# 4_cpu.net
KiCad netlist of a schematic drawn in Altium Designer
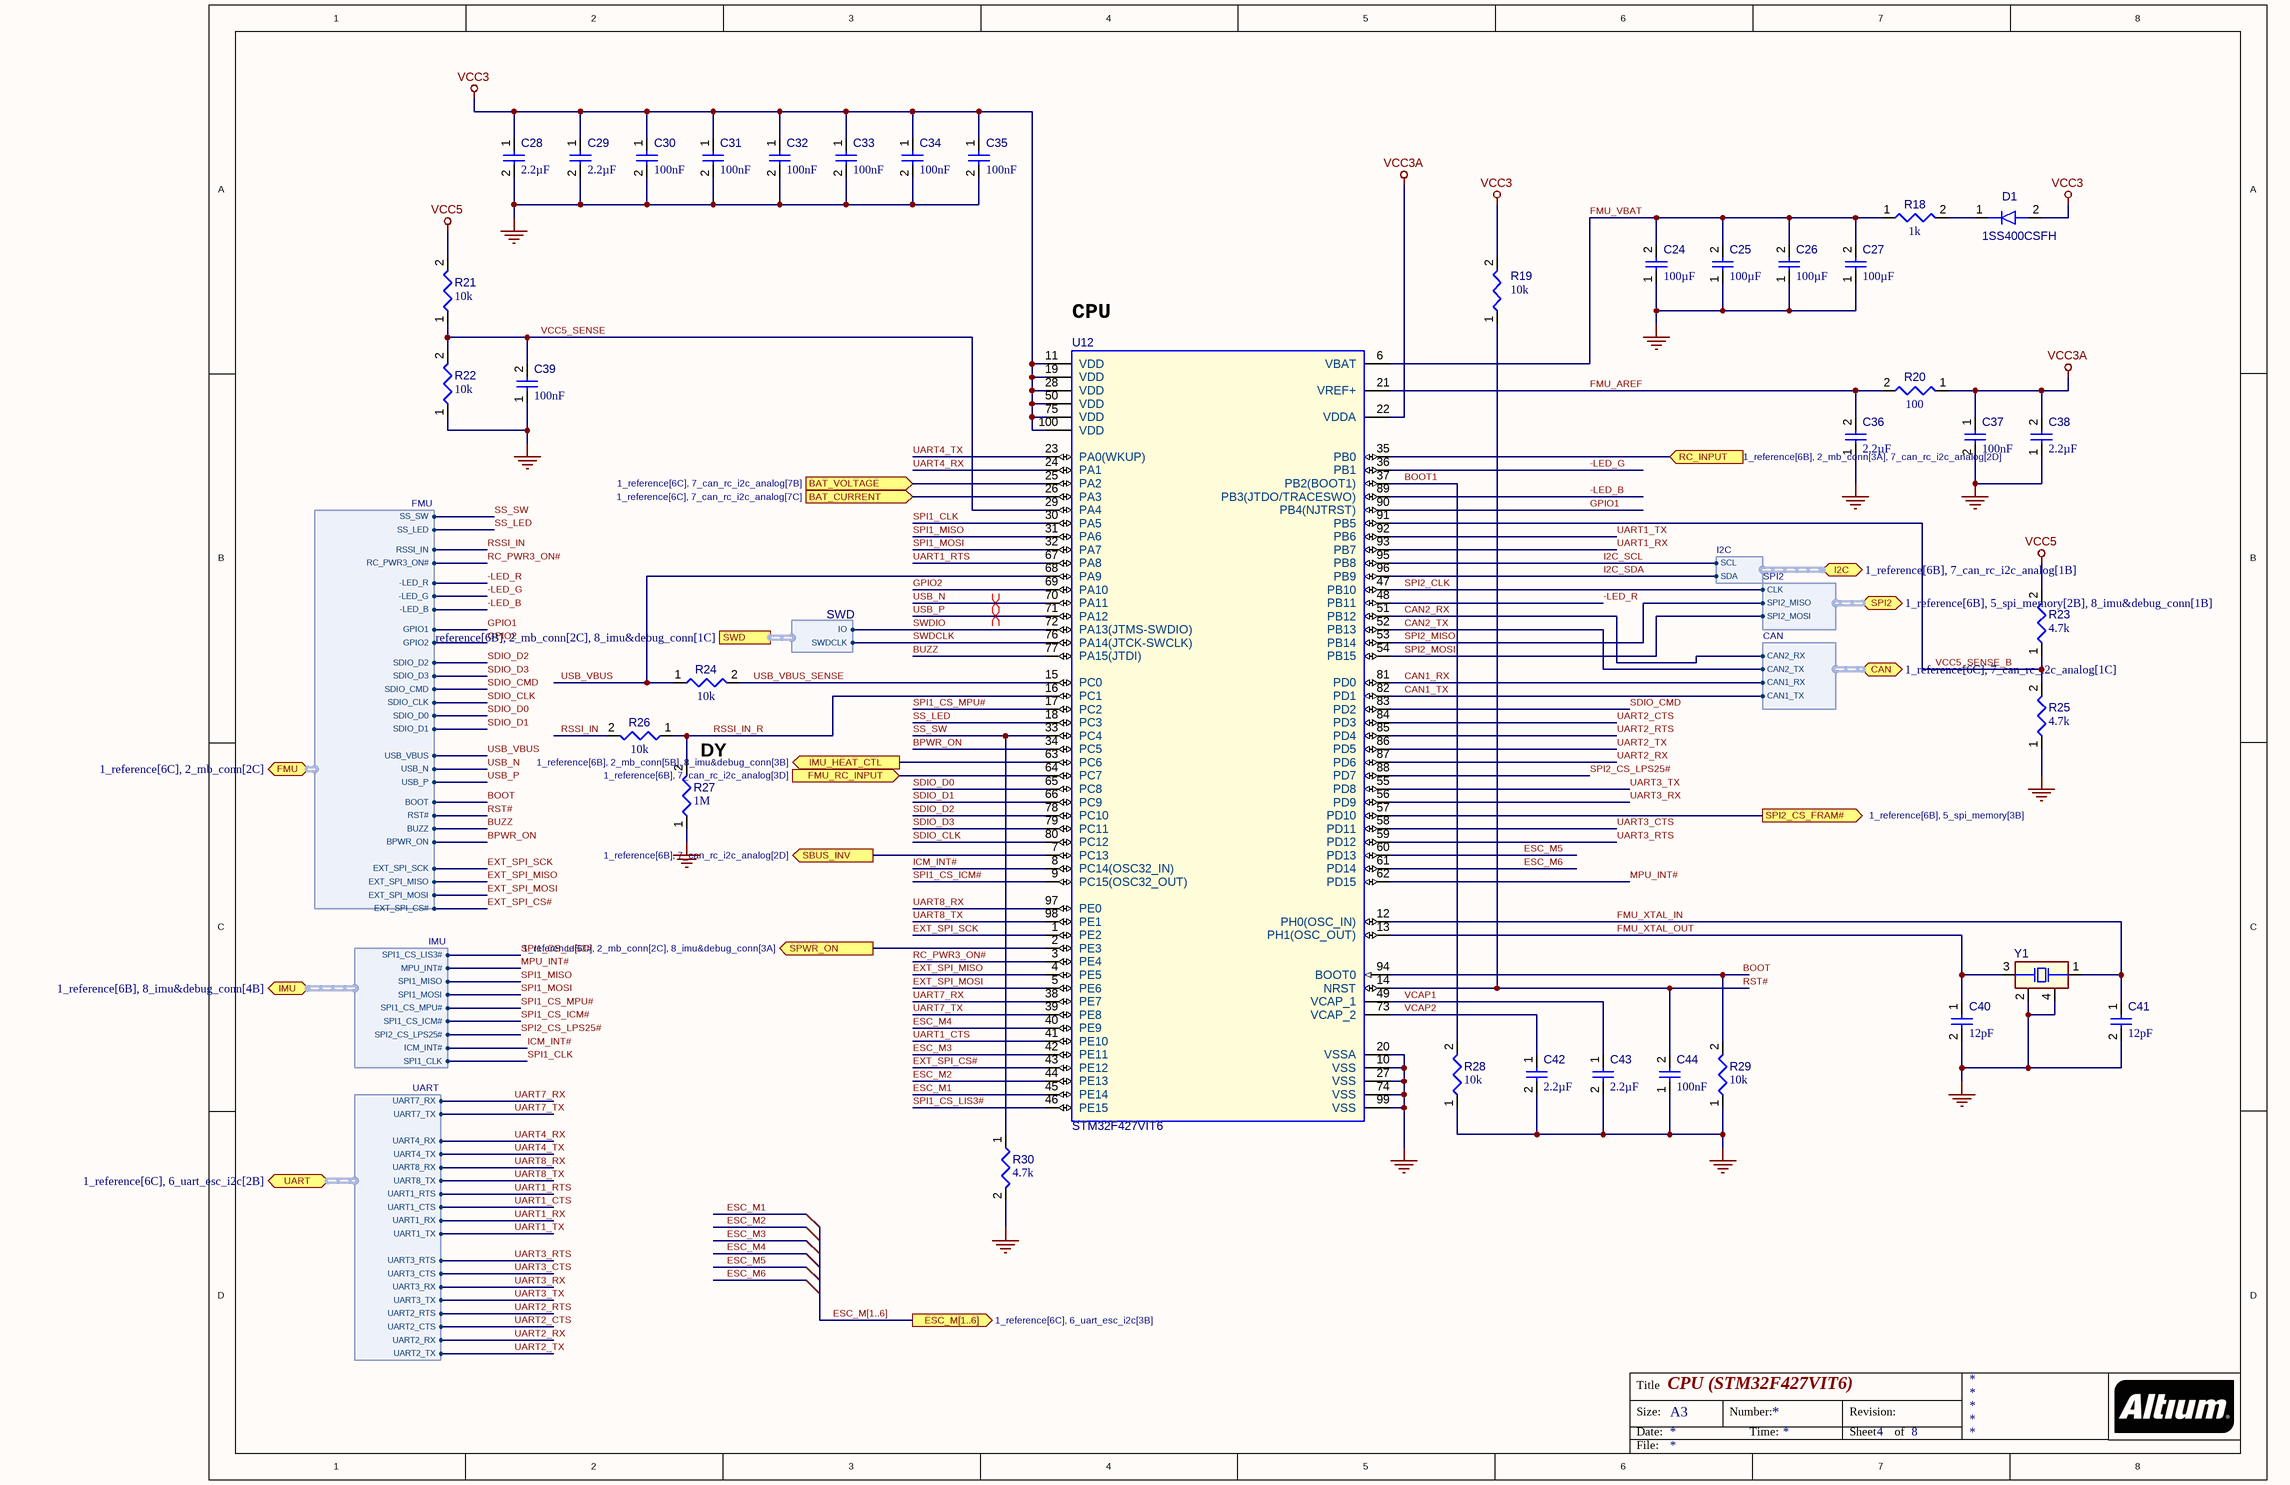
[diagram p0: 4_cpu.SchDoc]

(export (version "E")
  (design (tool "Eeschema 10.0.6"))
  (components
    (comp (ref "C24")
      (value "100µF")
      (footprint "CAPC0805(2012)145_L")
      (description "Chip Capacitor, 100µF +/-20%, 6.3V, 0805, Thickness 1.45 mm")
      (fields (field (name "TOLERANCE") "10%") (field (name "Comment") "Capacitor 100µF +/-20% 6.3V 0805"))
      (libsource (lib "<Company> Server") (part "CAP-NP-2"))
    )
    (comp (ref "C25")
      (value "100µF")
      (footprint "CAPC0805(2012)145_L")
      (description "Chip Capacitor, 100µF +/-20%, 6.3V, 0805, Thickness 1.45 mm")
      (fields (field (name "TOLERANCE") "10%") (field (name "Comment") "Capacitor 100µF +/-20% 6.3V 0805"))
      (libsource (lib "<Company> Server") (part "CAP-NP-2"))
    )
    (comp (ref "C26")
      (value "100µF")
      (footprint "CAPC0805(2012)145_L")
      (description "Chip Capacitor, 100µF +/-20%, 6.3V, 0805, Thickness 1.45 mm")
      (fields (field (name "TOLERANCE") "10%") (field (name "Comment") "Capacitor 100µF +/-20% 6.3V 0805"))
      (libsource (lib "<Company> Server") (part "CAP-NP-2"))
    )
    (comp (ref "C27")
      (value "100µF")
      (footprint "CAPC0805(2012)145_L")
      (description "Chip Capacitor, 100µF +/-20%, 6.3V, 0805, Thickness 1.45 mm")
      (fields (field (name "TOLERANCE") "10%") (field (name "Comment") "Capacitor 100µF +/-20% 6.3V 0805"))
      (libsource (lib "<Company> Server") (part "CAP-NP-2"))
    )
    (comp (ref "C28")
      (value "2.2µF")
      (footprint "CAPC0402(1005)60_L")
      (description "Chip Capacitor, 2,2µF +/-20%, 10V, 0402, Thickness 0.6 mm")
      (fields (field (name "TOLERANCE") "10%") (field (name "Comment") "Capacitor 2,2µF +/-20% 10V 0402"))
      (libsource (lib "<Company> Server") (part "CAP-NP-2"))
    )
    (comp (ref "C29")
      (value "2.2µF")
      (footprint "CAPC0402(1005)60_L")
      (description "Chip Capacitor, 2,2µF +/-20%, 10V, 0402, Thickness 0.6 mm")
      (fields (field (name "TOLERANCE") "10%") (field (name "Comment") "Capacitor 2,2µF +/-20% 10V 0402"))
      (libsource (lib "<Company> Server") (part "CAP-NP-2"))
    )
    (comp (ref "C30")
      (value "100nF")
      (footprint "CAPC0402(1005)60_L")
      (description "Chip Capacitor, 100nF +/-20%, 10V, 0402, Thickness 0.6 mm")
      (fields (field (name "TOLERANCE") "20%") (field (name "Comment") "Capacitor 100nF +/-20% 10V 0402"))
      (libsource (lib "<Company> Server") (part "CAP-NP-2"))
    )
    (comp (ref "C31")
      (value "100nF")
      (footprint "CAPC0402(1005)60_L")
      (description "Chip Capacitor, 100nF +/-20%, 10V, 0402, Thickness 0.6 mm")
      (fields (field (name "TOLERANCE") "20%") (field (name "Comment") "Capacitor 100nF +/-20% 10V 0402"))
      (libsource (lib "<Company> Server") (part "CAP-NP-2"))
    )
    (comp (ref "C32")
      (value "100nF")
      (footprint "CAPC0402(1005)60_L")
      (description "Chip Capacitor, 100nF +/-20%, 10V, 0402, Thickness 0.6 mm")
      (fields (field (name "TOLERANCE") "20%") (field (name "Comment") "Capacitor 100nF +/-20% 10V 0402"))
      (libsource (lib "<Company> Server") (part "CAP-NP-2"))
    )
    (comp (ref "C33")
      (value "100nF")
      (footprint "CAPC0402(1005)60_L")
      (description "Chip Capacitor, 100nF +/-20%, 10V, 0402, Thickness 0.6 mm")
      (fields (field (name "TOLERANCE") "20%") (field (name "Comment") "Capacitor 100nF +/-20% 10V 0402"))
      (libsource (lib "<Company> Server") (part "CAP-NP-2"))
    )
    (comp (ref "C34")
      (value "100nF")
      (footprint "CAPC0402(1005)60_L")
      (description "Chip Capacitor, 100nF +/-20%, 10V, 0402, Thickness 0.6 mm")
      (fields (field (name "TOLERANCE") "20%") (field (name "Comment") "Capacitor 100nF +/-20% 10V 0402"))
      (libsource (lib "<Company> Server") (part "CAP-NP-2"))
    )
    (comp (ref "C35")
      (value "100nF")
      (footprint "CAPC0402(1005)60_L")
      (description "Chip Capacitor, 100nF +/-20%, 10V, 0402, Thickness 0.6 mm")
      (fields (field (name "TOLERANCE") "20%") (field (name "Comment") "Capacitor 100nF +/-20% 10V 0402"))
      (libsource (lib "<Company> Server") (part "CAP-NP-2"))
    )
    (comp (ref "C36")
      (value "2.2µF")
      (footprint "CAPC0402(1005)60_L")
      (description "Chip Capacitor, 2,2µF +/-20%, 10V, 0402, Thickness 0.6 mm")
      (fields (field (name "TOLERANCE") "10%") (field (name "Comment") "Capacitor 2,2µF +/-20% 10V 0402"))
      (libsource (lib "<Company> Server") (part "CAP-NP-2"))
    )
    (comp (ref "C37")
      (value "100nF")
      (footprint "CAPC0402(1005)60_L")
      (description "Chip Capacitor, 100nF +/-20%, 10V, 0402, Thickness 0.6 mm")
      (fields (field (name "TOLERANCE") "20%") (field (name "Comment") "Capacitor 100nF +/-20% 10V 0402"))
      (libsource (lib "<Company> Server") (part "CAP-NP-2"))
    )
    (comp (ref "C38")
      (value "2.2µF")
      (footprint "CAPC0402(1005)60_L")
      (description "Chip Capacitor, 2,2µF +/-20%, 10V, 0402, Thickness 0.6 mm")
      (fields (field (name "TOLERANCE") "10%") (field (name "Comment") "Capacitor 2,2µF +/-20% 10V 0402"))
      (libsource (lib "<Company> Server") (part "CAP-NP-2"))
    )
    (comp (ref "C39")
      (value "100nF")
      (footprint "CAPC0402(1005)60_L")
      (description "Chip Capacitor, 100nF +/-20%, 10V, 0402, Thickness 0.6 mm")
      (fields (field (name "TOLERANCE") "20%") (field (name "Comment") "Capacitor 100nF +/-20% 10V 0402"))
      (libsource (lib "<Company> Server") (part "CAP-NP-2"))
    )
    (comp (ref "C40")
      (value "12pF")
      (footprint "CAPC0402(1005)33_L")
      (description "Chip Capacitor, 12pF +/-10%, 50V, 0402, Thickness 0.33 mm")
      (fields (field (name "TOLERANCE") "20%") (field (name "Comment") "Capacitor 12pF +/-10% 50V 0402"))
      (libsource (lib "<Company> Server") (part "CAP-NP-2"))
    )
    (comp (ref "C41")
      (value "12pF")
      (footprint "CAPC0402(1005)33_L")
      (description "Chip Capacitor, 12pF +/-10%, 50V, 0402, Thickness 0.33 mm")
      (fields (field (name "TOLERANCE") "20%") (field (name "Comment") "Capacitor 12pF +/-10% 50V 0402"))
      (libsource (lib "<Company> Server") (part "CAP-NP-2"))
    )
    (comp (ref "C42")
      (value "2.2µF")
      (footprint "CAPC0402(1005)60_L")
      (description "Chip Capacitor, 2,2µF +/-20%, 10V, 0402, Thickness 0.6 mm")
      (fields (field (name "TOLERANCE") "10%") (field (name "Comment") "Capacitor 2,2µF +/-20% 10V 0402"))
      (libsource (lib "<Company> Server") (part "CAP-NP-2"))
    )
    (comp (ref "C43")
      (value "2.2µF")
      (footprint "CAPC0402(1005)60_L")
      (description "Chip Capacitor, 2,2µF +/-20%, 10V, 0402, Thickness 0.6 mm")
      (fields (field (name "TOLERANCE") "10%") (field (name "Comment") "Capacitor 2,2µF +/-20% 10V 0402"))
      (libsource (lib "<Company> Server") (part "CAP-NP-2"))
    )
    (comp (ref "C44")
      (value "100nF")
      (footprint "CAPC0402(1005)60_L")
      (description "Chip Capacitor, 100nF +/-20%, 10V, 0402, Thickness 0.6 mm")
      (fields (field (name "TOLERANCE") "20%") (field (name "Comment") "Capacitor 100nF +/-20% 10V 0402"))
      (libsource (lib "<Company> Server") (part "CAP-NP-2"))
    )
    (comp (ref "D1")
      (value "1SS400CSFH")
      (footprint "ROHM-VMN2-2_V")
      (description "Switching Diode (High Speed Switching), 80 V, 100 mA, 2-Pin SOD-923, RoHS, Tape and Reel")
      (libsource (lib "<Company> Server") (part "D-KA-2"))
    )
    (comp (ref "R18")
      (value "1k")
      (footprint "RESC0402(1005)_L")
      (description "Chip Resistor, 1 kOhms, +/-5 %, 63 mW, -55 to 155 degC, 0402")
      (fields (field (name "TOLERANCE") "5%") (field (name "POWER") "63mW"))
      (libsource (lib "<Company> Server") (part "RES-2"))
    )
    (comp (ref "R19")
      (value "10k")
      (footprint "RESC0402(1005)_L")
      (description "Chip Resistor, 10 kOhms, +/-1 %, 63 mW, -55 to 125 degC, 0402")
      (fields (field (name "TOLERANCE") "1%") (field (name "POWER") "63mW"))
      (libsource (lib "<Company> Server") (part "RES-2"))
    )
    (comp (ref "R20")
      (value "100")
      (footprint "RESC0402(1005)_L")
      (description "Chip Resistor, 100 Ohms, +/-1 %, 63 mW, -55 to 155 degC, 0402")
      (fields (field (name "TOLERANCE") "1%") (field (name "POWER") "63mW"))
      (libsource (lib "<Company> Server") (part "RES-2"))
    )
    (comp (ref "R21")
      (value "10k")
      (footprint "RESC0402(1005)_L")
      (description "Chip Resistor, 10 kOhms, +/-1 %, 63 mW, -55 to 125 degC, 0402")
      (fields (field (name "TOLERANCE") "1%") (field (name "POWER") "63mW"))
      (libsource (lib "<Company> Server") (part "RES-2"))
    )
    (comp (ref "R22")
      (value "10k")
      (footprint "RESC0402(1005)_L")
      (description "Chip Resistor, 10 kOhms, +/-1 %, 63 mW, -55 to 125 degC, 0402")
      (fields (field (name "TOLERANCE") "1%") (field (name "POWER") "63mW"))
      (libsource (lib "<Company> Server") (part "RES-2"))
    )
    (comp (ref "R23")
      (value "4.7k")
      (footprint "RESC0402(1005)_L")
      (description "Chip Resistor, 4,7 kOhms, +/-1 %, 63 mW, -55 to 155 degC, 0402")
      (fields (field (name "TOLERANCE") "1%") (field (name "POWER") "63mW"))
      (libsource (lib "<Company> Server") (part "RES-2"))
    )
    (comp (ref "R24")
      (value "10k")
      (footprint "RESC0402(1005)_L")
      (description "Chip Resistor, 10 kOhms, +/-1 %, 63 mW, -55 to 125 degC, 0402")
      (fields (field (name "TOLERANCE") "1%") (field (name "POWER") "63mW"))
      (libsource (lib "<Company> Server") (part "RES-2"))
    )
    (comp (ref "R25")
      (value "4.7k")
      (footprint "RESC0402(1005)_L")
      (description "Chip Resistor, 4,7 kOhms, +/-1 %, 63 mW, -55 to 155 degC, 0402")
      (fields (field (name "TOLERANCE") "1%") (field (name "POWER") "63mW"))
      (libsource (lib "<Company> Server") (part "RES-2"))
    )
    (comp (ref "R26")
      (value "10k")
      (footprint "RESC0402(1005)_L")
      (description "Chip Resistor, 10 kOhms, +/-1 %, 63 mW, -55 to 125 degC, 0402")
      (fields (field (name "TOLERANCE") "1%") (field (name "POWER") "63mW"))
      (libsource (lib "<Company> Server") (part "RES-2"))
    )
    (comp (ref "R27")
      (value "1M")
      (footprint "RESC0402(1005)_L")
      (description "Chip Resistor, 1 MOhms, +/-5 %, 63 mW, -55 to 155 degC, 0402")
      (fields (field (name "TOLERANCE") "5%") (field (name "POWER") "63mW"))
      (libsource (lib "<Company> Server") (part "RES-2"))
    )
    (comp (ref "R28")
      (value "10k")
      (footprint "RESC0402(1005)_L")
      (description "Chip Resistor, 10 kOhms, +/-1 %, 63 mW, -55 to 125 degC, 0402")
      (fields (field (name "TOLERANCE") "1%") (field (name "POWER") "63mW"))
      (libsource (lib "<Company> Server") (part "RES-2"))
    )
    (comp (ref "R29")
      (value "10k")
      (footprint "RESC0402(1005)_L")
      (description "Chip Resistor, 10 kOhms, +/-1 %, 63 mW, -55 to 125 degC, 0402")
      (fields (field (name "TOLERANCE") "1%") (field (name "POWER") "63mW"))
      (libsource (lib "<Company> Server") (part "RES-2"))
    )
    (comp (ref "R30")
      (value "4.7k")
      (footprint "RESC0402(1005)_L")
      (description "Chip Resistor, 4,7 kOhms, +/-1 %, 63 mW, -55 to 155 degC, 0402")
      (fields (field (name "TOLERANCE") "1%") (field (name "POWER") "63mW"))
      (libsource (lib "<Company> Server") (part "RES-2"))
    )
    (comp (ref "U12")
      (value "STM32F427VIT6")
      (footprint "STM-LQFP100")
      (libsource (lib "<Company> Server") (part "CMP-00125-5"))
    )
    (comp (ref "Y1")
      (value "FA-12824.0000MF10Z-W3")
      (footprint "EPSON-FA-128_V")
      (description "Crystal, 24 MHz, +/- 10 ppm, -20 to 75 degC, 4-Pin SMD, RoHS, Tape and Reel")
      (libsource (lib "<Company> Server") (part "CMP-00014-7"))
    )
  )
  (nets
    (net (code "8") (name "/-LED_B") (class "Default")
      (node (ref "U12") (pin "89") (pinfunction "PB3(JTDO/TRACESWO)_89") (pintype "bidirectional"))
    )
    (net (code "9") (name "/-LED_G") (class "Default")
      (node (ref "U12") (pin "36") (pinfunction "PB1_36") (pintype "bidirectional"))
    )
    (net (code "10") (name "/-LED_R") (class "Default")
      (node (ref "U12") (pin "48") (pinfunction "PB11_48") (pintype "bidirectional"))
    )
    (net (code "11") (name "/BAT_CURRENT") (class "Default")
      (node (ref "U12") (pin "26") (pinfunction "PA3_26") (pintype "bidirectional"))
    )
    (net (code "12") (name "/BAT_VOLTAGE") (class "Default")
      (node (ref "U12") (pin "25") (pinfunction "PA2_25") (pintype "bidirectional"))
    )
    (net (code "13") (name "/BOOT") (class "Default")
      (node (ref "R29") (pin "2") (pinfunction "2_2") (pintype "passive"))
      (node (ref "U12") (pin "94") (pinfunction "BOOT0_94") (pintype "input"))
    )
    (net (code "14") (name "/BOOT1") (class "Default")
      (node (ref "R28") (pin "2") (pinfunction "2_2") (pintype "passive"))
      (node (ref "U12") (pin "37") (pinfunction "PB2(BOOT1)_37") (pintype "bidirectional"))
    )
    (net (code "15") (name "/BPWR_ON") (class "Default")
      (node (ref "U12") (pin "34") (pinfunction "PC5_34") (pintype "bidirectional"))
    )
    (net (code "16") (name "/BUZZ") (class "Default")
      (node (ref "U12") (pin "77") (pinfunction "PA15(JTDI)_77") (pintype "bidirectional"))
    )
    (net (code "17") (name "/CAN1_RX") (class "Default")
      (node (ref "U12") (pin "81") (pinfunction "PD0_81") (pintype "bidirectional"))
    )
    (net (code "18") (name "/CAN1_TX") (class "Default")
      (node (ref "U12") (pin "82") (pinfunction "PD1_82") (pintype "bidirectional"))
    )
    (net (code "19") (name "/CAN2_RX") (class "Default")
      (node (ref "U12") (pin "51") (pinfunction "PB12_51") (pintype "bidirectional"))
    )
    (net (code "20") (name "/CAN2_TX") (class "Default")
      (node (ref "U12") (pin "52") (pinfunction "PB13_52") (pintype "bidirectional"))
    )
    (net (code "21") (name "/ESC_M1") (class "Default")
      (node (ref "U12") (pin "45") (pinfunction "PE14_45") (pintype "bidirectional"))
    )
    (net (code "22") (name "/ESC_M2") (class "Default")
      (node (ref "U12") (pin "44") (pinfunction "PE13_44") (pintype "bidirectional"))
    )
    (net (code "23") (name "/ESC_M3") (class "Default")
      (node (ref "U12") (pin "42") (pinfunction "PE11_42") (pintype "bidirectional"))
    )
    (net (code "24") (name "/ESC_M4") (class "Default")
      (node (ref "U12") (pin "40") (pinfunction "PE9_40") (pintype "bidirectional"))
    )
    (net (code "25") (name "/ESC_M5") (class "Default")
      (node (ref "U12") (pin "60") (pinfunction "PD13_60") (pintype "bidirectional"))
    )
    (net (code "26") (name "/ESC_M6") (class "Default")
      (node (ref "U12") (pin "61") (pinfunction "PD14_61") (pintype "bidirectional"))
    )
    (net (code "28") (name "/EXT_SPI_CS#") (class "Default")
      (node (ref "U12") (pin "43") (pinfunction "PE12_43") (pintype "bidirectional"))
    )
    (net (code "29") (name "/EXT_SPI_MISO") (class "Default")
      (node (ref "U12") (pin "4") (pinfunction "PE5_4") (pintype "bidirectional"))
    )
    (net (code "30") (name "/EXT_SPI_MOSI") (class "Default")
      (node (ref "U12") (pin "5") (pinfunction "PE6_5") (pintype "bidirectional"))
    )
    (net (code "31") (name "/EXT_SPI_SCK") (class "Default")
      (node (ref "U12") (pin "1") (pinfunction "PE2_1") (pintype "bidirectional"))
    )
    (net (code "32") (name "/FMU_AREF") (class "Default")
      (node (ref "C36") (pin "2") (pinfunction "2_2") (pintype "passive"))
      (node (ref "R20") (pin "2") (pinfunction "2_2") (pintype "passive"))
      (node (ref "U12") (pin "21") (pinfunction "VREF+_21") (pintype "power_in"))
    )
    (net (code "33") (name "/FMU_RC_INPUT") (class "Default")
      (node (ref "U12") (pin "64") (pinfunction "PC7_64") (pintype "bidirectional"))
    )
    (net (code "34") (name "/FMU_VBAT") (class "Default")
      (node (ref "C24") (pin "2") (pinfunction "2_2") (pintype "passive"))
      (node (ref "C25") (pin "2") (pinfunction "2_2") (pintype "passive"))
      (node (ref "C26") (pin "2") (pinfunction "2_2") (pintype "passive"))
      (node (ref "C27") (pin "2") (pinfunction "2_2") (pintype "passive"))
      (node (ref "R18") (pin "1") (pinfunction "1_1") (pintype "passive"))
      (node (ref "U12") (pin "6") (pinfunction "VBAT_6") (pintype "power_in"))
    )
    (net (code "35") (name "/FMU_XTAL_IN") (class "Default")
      (node (ref "C41") (pin "1") (pinfunction "1_1") (pintype "passive"))
      (node (ref "U12") (pin "12") (pinfunction "PH0(OSC_IN)_12") (pintype "bidirectional"))
      (node (ref "Y1") (pin "1") (pinfunction "X1_1") (pintype "passive"))
    )
    (net (code "36") (name "/FMU_XTAL_OUT") (class "Default")
      (node (ref "C40") (pin "1") (pinfunction "1_1") (pintype "passive"))
      (node (ref "U12") (pin "13") (pinfunction "PH1(OSC_OUT)_13") (pintype "bidirectional"))
      (node (ref "Y1") (pin "3") (pinfunction "X2_3") (pintype "passive"))
    )
    (net (code "37") (name "/GPIO1") (class "Default")
      (node (ref "U12") (pin "90") (pinfunction "PB4(NJTRST)_90") (pintype "bidirectional"))
    )
    (net (code "38") (name "/GPIO2") (class "Default")
      (node (ref "U12") (pin "69") (pinfunction "PA10_69") (pintype "bidirectional"))
    )
    (net (code "39") (name "/I2C_SCL") (class "Default")
      (node (ref "U12") (pin "95") (pinfunction "PB8_95") (pintype "bidirectional"))
    )
    (net (code "40") (name "/I2C_SDA") (class "Default")
      (node (ref "U12") (pin "96") (pinfunction "PB9_96") (pintype "bidirectional"))
    )
    (net (code "41") (name "/ICM_INT#") (class "Default")
      (node (ref "U12") (pin "8") (pinfunction "PC14(OSC32_IN)_8") (pintype "bidirectional"))
    )
    (net (code "42") (name "/IMU_HEAT_CTL") (class "Default")
      (node (ref "U12") (pin "63") (pinfunction "PC6_63") (pintype "bidirectional"))
    )
    (net (code "43") (name "/MPU_INT#") (class "Default")
      (node (ref "U12") (pin "62") (pinfunction "PD15_62") (pintype "bidirectional"))
    )
    (net (code "44") (name "/RC_INPUT") (class "Default")
      (node (ref "U12") (pin "35") (pinfunction "PB0_35") (pintype "bidirectional"))
    )
    (net (code "45") (name "/RC_PWR3_ON#") (class "Default")
      (node (ref "U12") (pin "3") (pinfunction "PE4_3") (pintype "bidirectional"))
    )
    (net (code "46") (name "/RSSI_IN") (class "Default")
      (node (ref "R26") (pin "2") (pinfunction "2_2") (pintype "passive"))
    )
    (net (code "47") (name "/RSSI_IN_R") (class "Default")
      (node (ref "R26") (pin "1") (pinfunction "1_1") (pintype "passive"))
      (node (ref "R27") (pin "2") (pinfunction "2_2") (pintype "passive"))
      (node (ref "U12") (pin "16") (pinfunction "PC1_16") (pintype "bidirectional"))
    )
    (net (code "48") (name "/RST#") (class "Default")
      (node (ref "C44") (pin "2") (pinfunction "2_2") (pintype "passive"))
      (node (ref "R19") (pin "1") (pinfunction "1_1") (pintype "passive"))
      (node (ref "U12") (pin "14") (pinfunction "NRST_14") (pintype "bidirectional"))
    )
    (net (code "49") (name "/SBUS_INV") (class "Default")
      (node (ref "U12") (pin "7") (pinfunction "PC13_7") (pintype "bidirectional"))
    )
    (net (code "50") (name "/SDIO_CLK") (class "Default")
      (node (ref "U12") (pin "80") (pinfunction "PC12_80") (pintype "bidirectional"))
    )
    (net (code "51") (name "/SDIO_CMD") (class "Default")
      (node (ref "U12") (pin "83") (pinfunction "PD2_83") (pintype "bidirectional"))
    )
    (net (code "52") (name "/SDIO_D0") (class "Default")
      (node (ref "U12") (pin "65") (pinfunction "PC8_65") (pintype "bidirectional"))
    )
    (net (code "53") (name "/SDIO_D1") (class "Default")
      (node (ref "U12") (pin "66") (pinfunction "PC9_66") (pintype "bidirectional"))
    )
    (net (code "54") (name "/SDIO_D2") (class "Default")
      (node (ref "U12") (pin "78") (pinfunction "PC10_78") (pintype "bidirectional"))
    )
    (net (code "55") (name "/SDIO_D3") (class "Default")
      (node (ref "U12") (pin "79") (pinfunction "PC11_79") (pintype "bidirectional"))
    )
    (net (code "56") (name "/SPI1_CLK") (class "Default")
      (node (ref "U12") (pin "30") (pinfunction "PA5_30") (pintype "bidirectional"))
    )
    (net (code "57") (name "/SPI1_CS_ICM#") (class "Default")
      (node (ref "U12") (pin "9") (pinfunction "PC15(OSC32_OUT)_9") (pintype "bidirectional"))
    )
    (net (code "58") (name "/SPI1_CS_LIS3#") (class "Default")
      (node (ref "U12") (pin "46") (pinfunction "PE15_46") (pintype "bidirectional"))
    )
    (net (code "59") (name "/SPI1_CS_MPU#") (class "Default")
      (node (ref "U12") (pin "17") (pinfunction "PC2_17") (pintype "bidirectional"))
    )
    (net (code "60") (name "/SPI1_MISO") (class "Default")
      (node (ref "U12") (pin "31") (pinfunction "PA6_31") (pintype "bidirectional"))
    )
    (net (code "61") (name "/SPI1_MOSI") (class "Default")
      (node (ref "U12") (pin "32") (pinfunction "PA7_32") (pintype "bidirectional"))
    )
    (net (code "62") (name "/SPI2_CLK") (class "Default")
      (node (ref "U12") (pin "47") (pinfunction "PB10_47") (pintype "bidirectional"))
    )
    (net (code "63") (name "/SPI2_CS_FRAM#") (class "Default")
      (node (ref "U12") (pin "57") (pinfunction "PD10_57") (pintype "bidirectional"))
    )
    (net (code "64") (name "/SPI2_CS_LPS25#") (class "Default")
      (node (ref "U12") (pin "88") (pinfunction "PD7_88") (pintype "bidirectional"))
    )
    (net (code "65") (name "/SPI2_MISO") (class "Default")
      (node (ref "U12") (pin "53") (pinfunction "PB14_53") (pintype "bidirectional"))
    )
    (net (code "66") (name "/SPI2_MOSI") (class "Default")
      (node (ref "U12") (pin "54") (pinfunction "PB15_54") (pintype "bidirectional"))
    )
    (net (code "67") (name "/SPWR_ON") (class "Default")
      (node (ref "U12") (pin "2") (pinfunction "PE3_2") (pintype "bidirectional"))
    )
    (net (code "68") (name "/SS_LED") (class "Default")
      (node (ref "U12") (pin "18") (pinfunction "PC3_18") (pintype "bidirectional"))
    )
    (net (code "69") (name "/SS_SW") (class "Default")
      (node (ref "R30") (pin "1") (pinfunction "1_1") (pintype "passive"))
      (node (ref "U12") (pin "33") (pinfunction "PC4_33") (pintype "bidirectional"))
    )
    (net (code "70") (name "/SWDCLK") (class "Default")
      (node (ref "U12") (pin "76") (pinfunction "PA14(JTCK-SWCLK)_76") (pintype "bidirectional"))
    )
    (net (code "71") (name "/SWDIO") (class "Default")
      (node (ref "U12") (pin "72") (pinfunction "PA13(JTMS-SWDIO)_72") (pintype "bidirectional"))
    )
    (net (code "72") (name "/UART1_CTS") (class "Default")
      (node (ref "U12") (pin "41") (pinfunction "PE10_41") (pintype "bidirectional"))
    )
    (net (code "73") (name "/UART1_RTS") (class "Default")
      (node (ref "U12") (pin "67") (pinfunction "PA8_67") (pintype "bidirectional"))
    )
    (net (code "74") (name "/UART1_RX") (class "Default")
      (node (ref "U12") (pin "93") (pinfunction "PB7_93") (pintype "bidirectional"))
    )
    (net (code "75") (name "/UART1_TX") (class "Default")
      (node (ref "U12") (pin "92") (pinfunction "PB6_92") (pintype "bidirectional"))
    )
    (net (code "76") (name "/UART2_CTS") (class "Default")
      (node (ref "U12") (pin "84") (pinfunction "PD3_84") (pintype "bidirectional"))
    )
    (net (code "77") (name "/UART2_RTS") (class "Default")
      (node (ref "U12") (pin "85") (pinfunction "PD4_85") (pintype "bidirectional"))
    )
    (net (code "78") (name "/UART2_RX") (class "Default")
      (node (ref "U12") (pin "87") (pinfunction "PD6_87") (pintype "bidirectional"))
    )
    (net (code "79") (name "/UART2_TX") (class "Default")
      (node (ref "U12") (pin "86") (pinfunction "PD5_86") (pintype "bidirectional"))
    )
    (net (code "80") (name "/UART3_CTS") (class "Default")
      (node (ref "U12") (pin "58") (pinfunction "PD11_58") (pintype "bidirectional"))
    )
    (net (code "81") (name "/UART3_RTS") (class "Default")
      (node (ref "U12") (pin "59") (pinfunction "PD12_59") (pintype "bidirectional"))
    )
    (net (code "82") (name "/UART3_RX") (class "Default")
      (node (ref "U12") (pin "56") (pinfunction "PD9_56") (pintype "bidirectional"))
    )
    (net (code "83") (name "/UART3_TX") (class "Default")
      (node (ref "U12") (pin "55") (pinfunction "PD8_55") (pintype "bidirectional"))
    )
    (net (code "84") (name "/UART4_RX") (class "Default")
      (node (ref "U12") (pin "24") (pinfunction "PA1_24") (pintype "bidirectional"))
    )
    (net (code "85") (name "/UART4_TX") (class "Default")
      (node (ref "U12") (pin "23") (pinfunction "PA0(WKUP)_23") (pintype "bidirectional"))
    )
    (net (code "86") (name "/UART7_RX") (class "Default")
      (node (ref "U12") (pin "38") (pinfunction "PE7_38") (pintype "bidirectional"))
    )
    (net (code "87") (name "/UART7_TX") (class "Default")
      (node (ref "U12") (pin "39") (pinfunction "PE8_39") (pintype "bidirectional"))
    )
    (net (code "88") (name "/UART8_RX") (class "Default")
      (node (ref "U12") (pin "97") (pinfunction "PE0_97") (pintype "bidirectional"))
    )
    (net (code "89") (name "/UART8_TX") (class "Default")
      (node (ref "U12") (pin "98") (pinfunction "PE1_98") (pintype "bidirectional"))
    )
    (net (code "90") (name "/USB_N") (class "Default")
      (node (ref "U12") (pin "70") (pinfunction "PA11_70") (pintype "bidirectional"))
    )
    (net (code "91") (name "/USB_P") (class "Default")
      (node (ref "U12") (pin "71") (pinfunction "PA12_71") (pintype "bidirectional"))
    )
    (net (code "92") (name "/USB_VBUS") (class "Default")
      (node (ref "R24") (pin "1") (pinfunction "1_1") (pintype "passive"))
      (node (ref "U12") (pin "68") (pinfunction "PA9_68") (pintype "bidirectional"))
    )
    (net (code "93") (name "/USB_VBUS_SENSE") (class "Default")
      (node (ref "R24") (pin "2") (pinfunction "2_2") (pintype "passive"))
      (node (ref "U12") (pin "15") (pinfunction "PC0_15") (pintype "bidirectional"))
    )
    (net (code "94") (name "/VCAP1") (class "Default")
      (node (ref "C43") (pin "1") (pinfunction "1_1") (pintype "passive"))
      (node (ref "U12") (pin "49") (pinfunction "VCAP_1_49") (pintype "passive"))
    )
    (net (code "95") (name "/VCAP2") (class "Default")
      (node (ref "C42") (pin "1") (pinfunction "1_1") (pintype "passive"))
      (node (ref "U12") (pin "73") (pinfunction "VCAP_2_73") (pintype "passive"))
    )
    (net (code "96") (name "/VCC5_SENSE") (class "Default")
      (node (ref "C39") (pin "2") (pinfunction "2_2") (pintype "passive"))
      (node (ref "R21") (pin "1") (pinfunction "1_1") (pintype "passive"))
      (node (ref "R22") (pin "2") (pinfunction "2_2") (pintype "passive"))
      (node (ref "U12") (pin "29") (pinfunction "PA4_29") (pintype "bidirectional"))
    )
    (net (code "97") (name "/VCC5_SENSE_B") (class "Default")
      (node (ref "R23") (pin "1") (pinfunction "1_1") (pintype "passive"))
      (node (ref "R25") (pin "2") (pinfunction "2_2") (pintype "passive"))
      (node (ref "U12") (pin "91") (pinfunction "PB5_91") (pintype "bidirectional"))
    )
    (net (code "105") (name "GND") (class "Default")
      (node (ref "C24") (pin "1") (pinfunction "1_1") (pintype "passive"))
      (node (ref "C25") (pin "1") (pinfunction "1_1") (pintype "passive"))
      (node (ref "C26") (pin "1") (pinfunction "1_1") (pintype "passive"))
      (node (ref "C27") (pin "1") (pinfunction "1_1") (pintype "passive"))
      (node (ref "C28") (pin "2") (pinfunction "2_2") (pintype "passive"))
      (node (ref "C29") (pin "2") (pinfunction "2_2") (pintype "passive"))
      (node (ref "C30") (pin "2") (pinfunction "2_2") (pintype "passive"))
      (node (ref "C31") (pin "2") (pinfunction "2_2") (pintype "passive"))
      (node (ref "C32") (pin "2") (pinfunction "2_2") (pintype "passive"))
      (node (ref "C33") (pin "2") (pinfunction "2_2") (pintype "passive"))
      (node (ref "C34") (pin "2") (pinfunction "2_2") (pintype "passive"))
      (node (ref "C35") (pin "2") (pinfunction "2_2") (pintype "passive"))
      (node (ref "C36") (pin "1") (pinfunction "1_1") (pintype "passive"))
      (node (ref "C37") (pin "2") (pinfunction "2_2") (pintype "passive"))
      (node (ref "C38") (pin "1") (pinfunction "1_1") (pintype "passive"))
      (node (ref "C39") (pin "1") (pinfunction "1_1") (pintype "passive"))
      (node (ref "C40") (pin "2") (pinfunction "2_2") (pintype "passive"))
      (node (ref "C41") (pin "2") (pinfunction "2_2") (pintype "passive"))
      (node (ref "C42") (pin "2") (pinfunction "2_2") (pintype "passive"))
      (node (ref "C43") (pin "2") (pinfunction "2_2") (pintype "passive"))
      (node (ref "C44") (pin "1") (pinfunction "1_1") (pintype "passive"))
      (node (ref "R22") (pin "1") (pinfunction "1_1") (pintype "passive"))
      (node (ref "R25") (pin "1") (pinfunction "1_1") (pintype "passive"))
      (node (ref "R27") (pin "1") (pinfunction "1_1") (pintype "passive"))
      (node (ref "R28") (pin "1") (pinfunction "1_1") (pintype "passive"))
      (node (ref "R29") (pin "1") (pinfunction "1_1") (pintype "passive"))
      (node (ref "R30") (pin "2") (pinfunction "2_2") (pintype "passive"))
      (node (ref "U12") (pin "10") (pinfunction "VSS_10") (pintype "power_in"))
      (node (ref "U12") (pin "20") (pinfunction "VSSA_20") (pintype "power_in"))
      (node (ref "U12") (pin "27") (pinfunction "VSS_27") (pintype "power_in"))
      (node (ref "U12") (pin "74") (pinfunction "VSS_74") (pintype "power_in"))
      (node (ref "U12") (pin "99") (pinfunction "VSS_99") (pintype "power_in"))
      (node (ref "Y1") (pin "2") (pinfunction "NC_2") (pintype "power_in"))
      (node (ref "Y1") (pin "4") (pinfunction "NC_4") (pintype "power_in"))
    )
    (net (code "106") (name "Net-(D1-K)") (class "Default")
      (node (ref "D1") (pin "1") (pinfunction "K_1") (pintype "passive"))
      (node (ref "R18") (pin "2") (pinfunction "2_2") (pintype "passive"))
    )
    (net (code "107") (name "VCC3") (class "Default")
      (node (ref "C28") (pin "1") (pinfunction "1_1") (pintype "passive"))
      (node (ref "C29") (pin "1") (pinfunction "1_1") (pintype "passive"))
      (node (ref "C30") (pin "1") (pinfunction "1_1") (pintype "passive"))
      (node (ref "C31") (pin "1") (pinfunction "1_1") (pintype "passive"))
      (node (ref "C32") (pin "1") (pinfunction "1_1") (pintype "passive"))
      (node (ref "C33") (pin "1") (pinfunction "1_1") (pintype "passive"))
      (node (ref "C34") (pin "1") (pinfunction "1_1") (pintype "passive"))
      (node (ref "C35") (pin "1") (pinfunction "1_1") (pintype "passive"))
      (node (ref "D1") (pin "2") (pinfunction "A_2") (pintype "passive"))
      (node (ref "R19") (pin "2") (pinfunction "2_2") (pintype "passive"))
      (node (ref "U12") (pin "100") (pinfunction "VDD_100") (pintype "power_in"))
      (node (ref "U12") (pin "11") (pinfunction "VDD_11") (pintype "power_in"))
      (node (ref "U12") (pin "19") (pinfunction "VDD_19") (pintype "power_in"))
      (node (ref "U12") (pin "28") (pinfunction "VDD_28") (pintype "power_in"))
      (node (ref "U12") (pin "50") (pinfunction "VDD_50") (pintype "power_in"))
      (node (ref "U12") (pin "75") (pinfunction "VDD_75") (pintype "power_in"))
    )
    (net (code "108") (name "VCC3A") (class "Default")
      (node (ref "C37") (pin "1") (pinfunction "1_1") (pintype "passive"))
      (node (ref "C38") (pin "2") (pinfunction "2_2") (pintype "passive"))
      (node (ref "R20") (pin "1") (pinfunction "1_1") (pintype "passive"))
      (node (ref "U12") (pin "22") (pinfunction "VDDA_22") (pintype "power_in"))
    )
    (net (code "109") (name "VCC5") (class "Default")
      (node (ref "R21") (pin "2") (pinfunction "2_2") (pintype "passive"))
      (node (ref "R23") (pin "2") (pinfunction "2_2") (pintype "passive"))
    )
  )
)
